# Keg_Cop_-_Devel_SMD.net
KiCad netlist of a schematic drawn in EAGLE
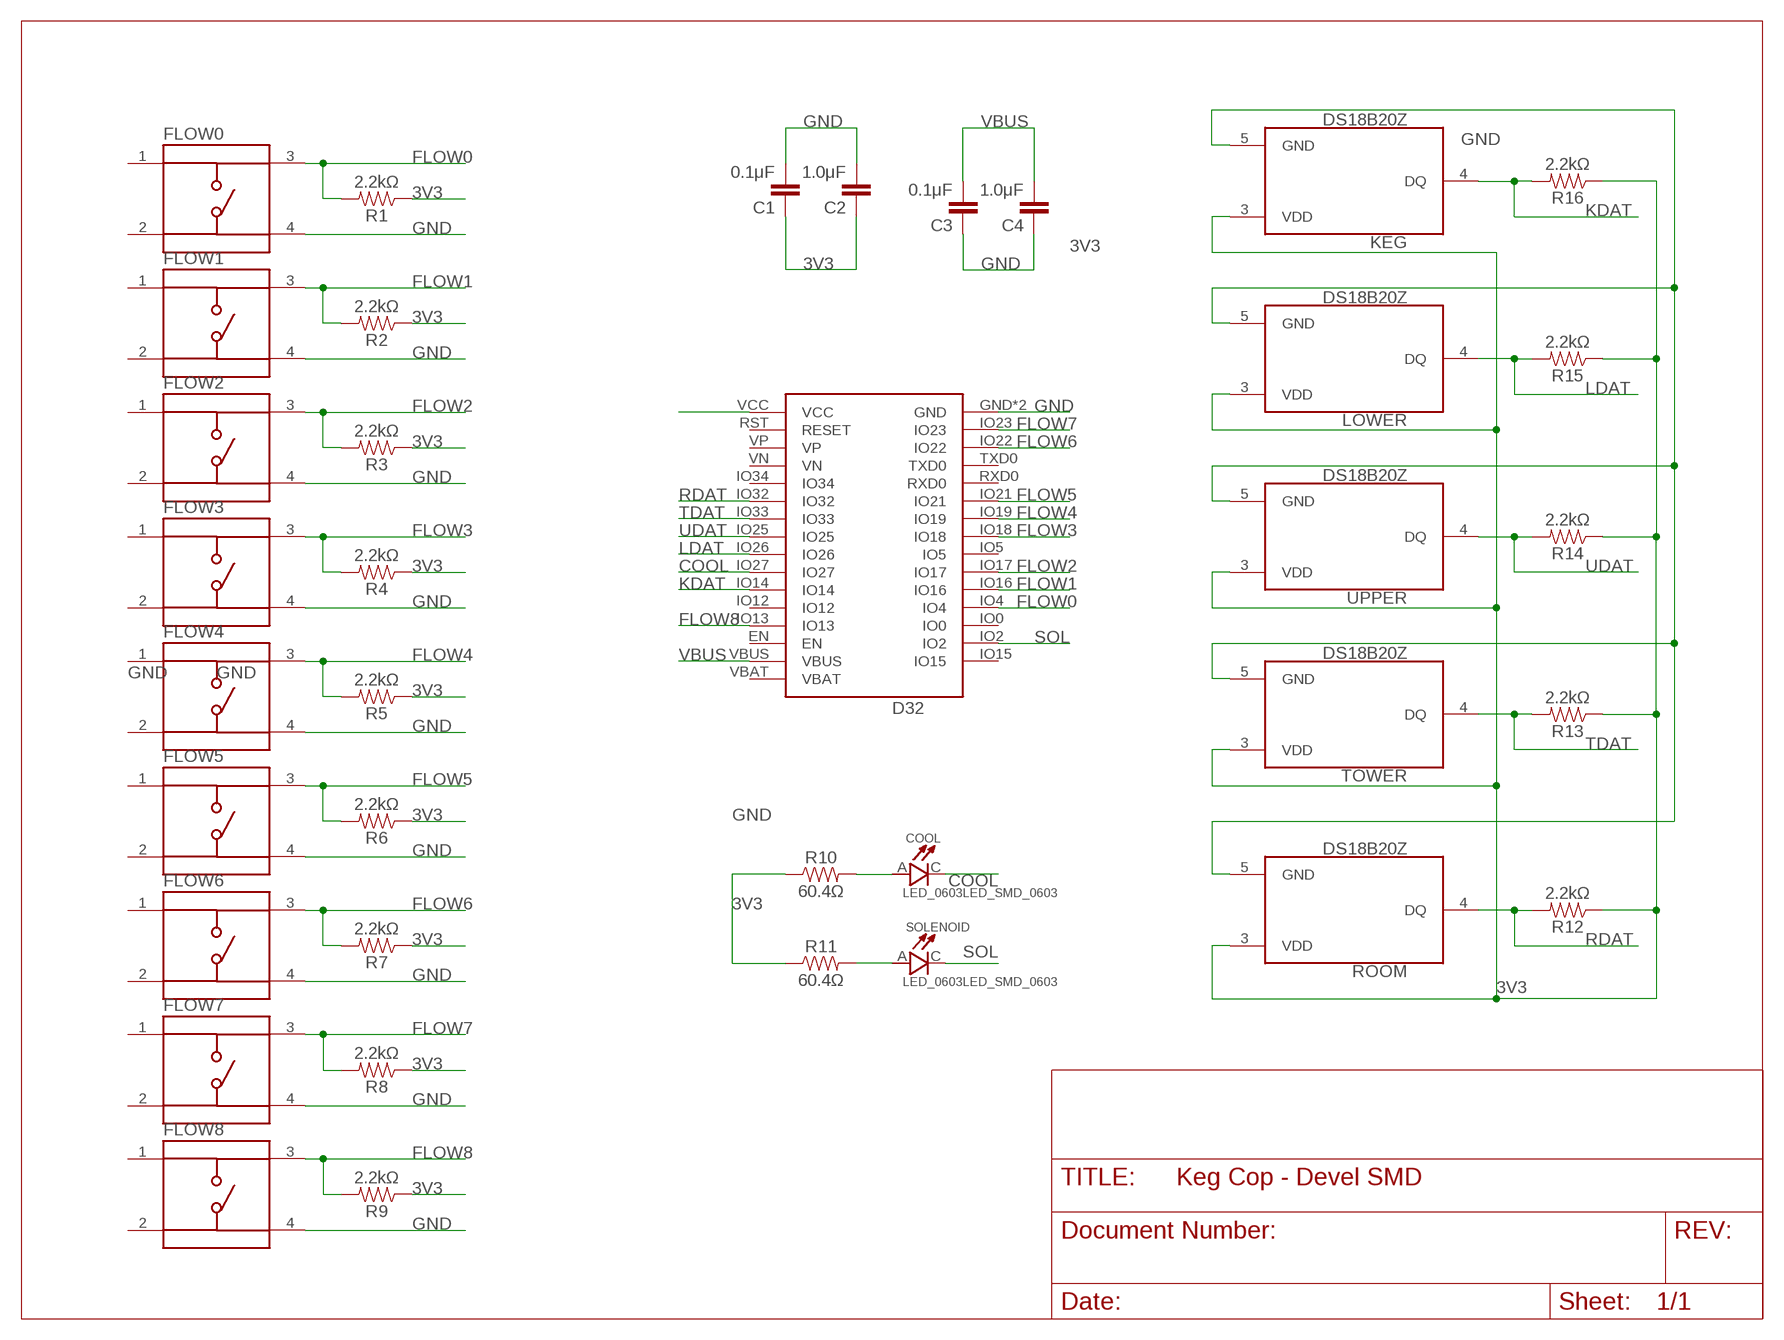
[diagram p0: schematic, sheet 1]

(export (version "E")
  (design (tool "Eeschema 10.0.6"))
  (components
    (comp (ref "C1")
      (value "0.1μF")
      (footprint "eagle-import:SMD-0805")
      (libsource (lib "eagle-import") (part "CAP_SMD0805"))
    )
    (comp (ref "C2")
      (value "1.0μF")
      (footprint "eagle-import:SMD-0805")
      (libsource (lib "eagle-import") (part "CAP_SMD0805"))
    )
    (comp (ref "C3")
      (value "0.1μF")
      (footprint "eagle-import:SMD-0805")
      (libsource (lib "eagle-import") (part "CAP_SMD0805"))
    )
    (comp (ref "C4")
      (value "1.0μF")
      (footprint "eagle-import:SMD-0805")
      (libsource (lib "eagle-import") (part "CAP_SMD0805"))
    )
    (comp (ref "COOL")
      (value "LED_0603LED_SMD_0603")
      (footprint "eagle-import:LED_SMD_0603")
      (fields (field (name "LCSC_PART") "C2286"))
      (libsource (lib "eagle-import") (part "LED_0603LED_SMD_0603"))
    )
    (comp (ref "D32")
      (value "Lolin D32")
      (footprint "eagle-import:D32_NO_BATT")
      (fields (field (name "SPICEPREFIX") "X"))
      (libsource (lib "eagle-import") (part "WEMOS-D32D32_NO_BATT"))
    )
    (comp (ref "FLOW0")
      (value "TS08-66-43-BK-160-SMT-67")
      (footprint "eagle-import:SW_TS08-66-43-BK-160-SMT-67")
      (fields
        (field (name "LCSC_PART") "C2888744")
        (field (name "MF") "BZCN")
        (field (name "MP") "TSD003B04326A03")
      )
      (libsource (lib "eagle-import") (part "TS08-66-43-BK-160-SMT-67"))
    )
    (comp (ref "FLOW1")
      (value "TS08-66-43-BK-160-SMT-67")
      (footprint "eagle-import:SW_TS08-66-43-BK-160-SMT-67")
      (fields
        (field (name "LCSC_PART") "C2888744")
        (field (name "MF") "BZCN")
        (field (name "MP") "TSD003B04326A03")
      )
      (libsource (lib "eagle-import") (part "TS08-66-43-BK-160-SMT-67"))
    )
    (comp (ref "FLOW2")
      (value "TS08-66-43-BK-160-SMT-67")
      (footprint "eagle-import:SW_TS08-66-43-BK-160-SMT-67")
      (fields
        (field (name "LCSC_PART") "C2888744")
        (field (name "MF") "BZCN")
        (field (name "MP") "TSD003B04326A03")
      )
      (libsource (lib "eagle-import") (part "TS08-66-43-BK-160-SMT-67"))
    )
    (comp (ref "FLOW3")
      (value "TS08-66-43-BK-160-SMT-67")
      (footprint "eagle-import:SW_TS08-66-43-BK-160-SMT-67")
      (fields
        (field (name "LCSC_PART") "C2888744")
        (field (name "MF") "BZCN")
        (field (name "MP") "TSD003B04326A03")
      )
      (libsource (lib "eagle-import") (part "TS08-66-43-BK-160-SMT-67"))
    )
    (comp (ref "FLOW4")
      (value "TS08-66-43-BK-160-SMT-67")
      (footprint "eagle-import:SW_TS08-66-43-BK-160-SMT-67")
      (fields
        (field (name "LCSC_PART") "C2888744")
        (field (name "MF") "BZCN")
        (field (name "MP") "TSD003B04326A03")
      )
      (libsource (lib "eagle-import") (part "TS08-66-43-BK-160-SMT-67"))
    )
    (comp (ref "FLOW5")
      (value "TS08-66-43-BK-160-SMT-67")
      (footprint "eagle-import:SW_TS08-66-43-BK-160-SMT-67")
      (fields
        (field (name "LCSC_PART") "C2888744")
        (field (name "MF") "BZCN")
        (field (name "MP") "TSD003B04326A03")
      )
      (libsource (lib "eagle-import") (part "TS08-66-43-BK-160-SMT-67"))
    )
    (comp (ref "FLOW6")
      (value "TS08-66-43-BK-160-SMT-67")
      (footprint "eagle-import:SW_TS08-66-43-BK-160-SMT-67")
      (fields
        (field (name "LCSC_PART") "C2888744")
        (field (name "MF") "BZCN")
        (field (name "MP") "TSD003B04326A03")
      )
      (libsource (lib "eagle-import") (part "TS08-66-43-BK-160-SMT-67"))
    )
    (comp (ref "FLOW7")
      (value "TS08-66-43-BK-160-SMT-67")
      (footprint "eagle-import:SW_TS08-66-43-BK-160-SMT-67")
      (fields
        (field (name "LCSC_PART") "C2888744")
        (field (name "MF") "BZCN")
        (field (name "MP") "TSD003B04326A03")
      )
      (libsource (lib "eagle-import") (part "TS08-66-43-BK-160-SMT-67"))
    )
    (comp (ref "FLOW8")
      (value "TS08-66-43-BK-160-SMT-67")
      (footprint "eagle-import:SW_TS08-66-43-BK-160-SMT-67")
      (fields
        (field (name "LCSC_PART") "C2888744")
        (field (name "MF") "BZCN")
        (field (name "MP") "TSD003B04326A03")
      )
      (libsource (lib "eagle-import") (part "TS08-66-43-BK-160-SMT-67"))
    )
    (comp (ref "KEG")
      (value "DS18B20Z")
      (footprint "eagle-import:SOIC127P600X175-8N")
      (fields (field (name "LCSC_PART") "C695837") (field (name "MF") "Maxim Integrated"))
      (libsource (lib "eagle-import") (part "DS18B20Z"))
    )
    (comp (ref "LOWER")
      (value "DS18B20Z")
      (footprint "eagle-import:SOIC127P600X175-8N")
      (fields (field (name "LCSC_PART") "C695837") (field (name "MF") "Maxim Integrated"))
      (libsource (lib "eagle-import") (part "DS18B20Z"))
    )
    (comp (ref "R1")
      (value "2.2kΩ")
      (footprint "eagle-import:SMD-0805")
      (libsource (lib "eagle-import") (part "RES_SMD0805"))
    )
    (comp (ref "R2")
      (value "2.2kΩ")
      (footprint "eagle-import:SMD-0805")
      (libsource (lib "eagle-import") (part "RES_SMD0805"))
    )
    (comp (ref "R3")
      (value "2.2kΩ")
      (footprint "eagle-import:SMD-0805")
      (libsource (lib "eagle-import") (part "RES_SMD0805"))
    )
    (comp (ref "R4")
      (value "2.2kΩ")
      (footprint "eagle-import:SMD-0805")
      (libsource (lib "eagle-import") (part "RES_SMD0805"))
    )
    (comp (ref "R5")
      (value "2.2kΩ")
      (footprint "eagle-import:SMD-0805")
      (libsource (lib "eagle-import") (part "RES_SMD0805"))
    )
    (comp (ref "R6")
      (value "2.2kΩ")
      (footprint "eagle-import:SMD-0805")
      (libsource (lib "eagle-import") (part "RES_SMD0805"))
    )
    (comp (ref "R7")
      (value "2.2kΩ")
      (footprint "eagle-import:SMD-0805")
      (libsource (lib "eagle-import") (part "RES_SMD0805"))
    )
    (comp (ref "R8")
      (value "2.2kΩ")
      (footprint "eagle-import:SMD-0805")
      (libsource (lib "eagle-import") (part "RES_SMD0805"))
    )
    (comp (ref "R9")
      (value "2.2kΩ")
      (footprint "eagle-import:SMD-0805")
      (libsource (lib "eagle-import") (part "RES_SMD0805"))
    )
    (comp (ref "R10")
      (value "60.4Ω")
      (footprint "eagle-import:SMD-0805")
      (libsource (lib "eagle-import") (part "RES_SMD0805"))
    )
    (comp (ref "R11")
      (value "60.4Ω")
      (footprint "eagle-import:SMD-0805")
      (libsource (lib "eagle-import") (part "RES_SMD0805"))
    )
    (comp (ref "R12")
      (value "2.2kΩ")
      (footprint "eagle-import:SMD-0805")
      (libsource (lib "eagle-import") (part "RES_SMD0805"))
    )
    (comp (ref "R13")
      (value "2.2kΩ")
      (footprint "eagle-import:SMD-0805")
      (libsource (lib "eagle-import") (part "RES_SMD0805"))
    )
    (comp (ref "R14")
      (value "2.2kΩ")
      (footprint "eagle-import:SMD-0805")
      (libsource (lib "eagle-import") (part "RES_SMD0805"))
    )
    (comp (ref "R15")
      (value "2.2kΩ")
      (footprint "eagle-import:SMD-0805")
      (libsource (lib "eagle-import") (part "RES_SMD0805"))
    )
    (comp (ref "R16")
      (value "2.2kΩ")
      (footprint "eagle-import:SMD-0805")
      (libsource (lib "eagle-import") (part "RES_SMD0805"))
    )
    (comp (ref "ROOM")
      (value "DS18B20Z")
      (footprint "eagle-import:SOIC127P600X175-8N")
      (fields (field (name "LCSC_PART") "C695837") (field (name "MF") "Maxim Integrated"))
      (libsource (lib "eagle-import") (part "DS18B20Z"))
    )
    (comp (ref "SOLENOID")
      (value "LED_0603LED_SMD_0603")
      (footprint "eagle-import:LED_SMD_0603")
      (fields (field (name "LCSC_PART") "C2286"))
      (libsource (lib "eagle-import") (part "LED_0603LED_SMD_0603"))
    )
    (comp (ref "TOWER")
      (value "DS18B20Z")
      (footprint "eagle-import:SOIC127P600X175-8N")
      (fields (field (name "LCSC_PART") "C695837") (field (name "MF") "Maxim Integrated"))
      (libsource (lib "eagle-import") (part "DS18B20Z"))
    )
    (comp (ref "UPPER")
      (value "DS18B20Z")
      (footprint "eagle-import:SOIC127P600X175-8N")
      (fields (field (name "LCSC_PART") "C695837") (field (name "MF") "Maxim Integrated"))
      (libsource (lib "eagle-import") (part "DS18B20Z"))
    )
  )
  (nets
    (net (code "1") (name "/3V3") (class "Default")
      (node (ref "C1") (pin "1") (pinfunction "1_1") (pintype "passive"))
      (node (ref "C2") (pin "1") (pinfunction "1_1") (pintype "passive"))
      (node (ref "D32") (pin "VCC") (pinfunction "VCC_VCC") (pintype "power_in"))
      (node (ref "KEG") (pin "3") (pinfunction "VDD_3") (pintype "power_in"))
      (node (ref "LOWER") (pin "3") (pinfunction "VDD_3") (pintype "power_in"))
      (node (ref "R1") (pin "1") (pinfunction "1_1") (pintype "passive"))
      (node (ref "R10") (pin "1") (pinfunction "1_1") (pintype "passive"))
      (node (ref "R11") (pin "1") (pinfunction "1_1") (pintype "passive"))
      (node (ref "R12") (pin "1") (pinfunction "1_1") (pintype "passive"))
      (node (ref "R13") (pin "1") (pinfunction "1_1") (pintype "passive"))
      (node (ref "R14") (pin "1") (pinfunction "1_1") (pintype "passive"))
      (node (ref "R15") (pin "1") (pinfunction "1_1") (pintype "passive"))
      (node (ref "R16") (pin "1") (pinfunction "1_1") (pintype "passive"))
      (node (ref "R2") (pin "1") (pinfunction "1_1") (pintype "passive"))
      (node (ref "R3") (pin "1") (pinfunction "1_1") (pintype "passive"))
      (node (ref "R4") (pin "1") (pinfunction "1_1") (pintype "passive"))
      (node (ref "R5") (pin "1") (pinfunction "1_1") (pintype "passive"))
      (node (ref "R6") (pin "1") (pinfunction "1_1") (pintype "passive"))
      (node (ref "R7") (pin "1") (pinfunction "1_1") (pintype "passive"))
      (node (ref "R8") (pin "1") (pinfunction "1_1") (pintype "passive"))
      (node (ref "R9") (pin "1") (pinfunction "1_1") (pintype "passive"))
      (node (ref "ROOM") (pin "3") (pinfunction "VDD_3") (pintype "power_in"))
      (node (ref "TOWER") (pin "3") (pinfunction "VDD_3") (pintype "power_in"))
      (node (ref "UPPER") (pin "3") (pinfunction "VDD_3") (pintype "power_in"))
    )
    (net (code "2") (name "/COOL") (class "Default")
      (node (ref "COOL") (pin "C") (pinfunction "C_C") (pintype "passive"))
      (node (ref "D32") (pin "IO27") (pinfunction "IO27_IO27") (pintype "bidirectional"))
    )
    (net (code "3") (name "/FLOW0") (class "Default")
      (node (ref "D32") (pin "IO4") (pinfunction "IO4_IO4") (pintype "bidirectional"))
      (node (ref "FLOW0") (pin "3") (pinfunction "3_3") (pintype "passive"))
      (node (ref "R1") (pin "2") (pinfunction "2_2") (pintype "passive"))
    )
    (net (code "4") (name "/FLOW1") (class "Default")
      (node (ref "D32") (pin "IO16") (pinfunction "IO16_IO16") (pintype "bidirectional"))
      (node (ref "FLOW1") (pin "3") (pinfunction "3_3") (pintype "passive"))
      (node (ref "R2") (pin "2") (pinfunction "2_2") (pintype "passive"))
    )
    (net (code "5") (name "/FLOW2") (class "Default")
      (node (ref "D32") (pin "IO17") (pinfunction "IO17_IO17") (pintype "bidirectional"))
      (node (ref "FLOW2") (pin "3") (pinfunction "3_3") (pintype "passive"))
      (node (ref "R3") (pin "2") (pinfunction "2_2") (pintype "passive"))
    )
    (net (code "6") (name "/FLOW3") (class "Default")
      (node (ref "D32") (pin "IO18") (pinfunction "IO18_IO18") (pintype "bidirectional"))
      (node (ref "FLOW3") (pin "3") (pinfunction "3_3") (pintype "passive"))
      (node (ref "R4") (pin "2") (pinfunction "2_2") (pintype "passive"))
    )
    (net (code "7") (name "/FLOW4") (class "Default")
      (node (ref "D32") (pin "IO19") (pinfunction "IO19_IO19") (pintype "bidirectional"))
      (node (ref "FLOW4") (pin "3") (pinfunction "3_3") (pintype "passive"))
      (node (ref "R5") (pin "2") (pinfunction "2_2") (pintype "passive"))
    )
    (net (code "8") (name "/FLOW5") (class "Default")
      (node (ref "D32") (pin "IO21") (pinfunction "IO21_IO21") (pintype "bidirectional"))
      (node (ref "FLOW5") (pin "3") (pinfunction "3_3") (pintype "passive"))
      (node (ref "R6") (pin "2") (pinfunction "2_2") (pintype "passive"))
    )
    (net (code "9") (name "/FLOW6") (class "Default")
      (node (ref "D32") (pin "IO22") (pinfunction "IO22_IO22") (pintype "bidirectional"))
      (node (ref "FLOW6") (pin "3") (pinfunction "3_3") (pintype "passive"))
      (node (ref "R7") (pin "2") (pinfunction "2_2") (pintype "passive"))
    )
    (net (code "10") (name "/FLOW7") (class "Default")
      (node (ref "D32") (pin "IO23") (pinfunction "IO23_IO23") (pintype "bidirectional"))
      (node (ref "FLOW7") (pin "3") (pinfunction "3_3") (pintype "passive"))
      (node (ref "R8") (pin "2") (pinfunction "2_2") (pintype "passive"))
    )
    (net (code "11") (name "/FLOW8") (class "Default")
      (node (ref "D32") (pin "IO13") (pinfunction "IO13_IO13") (pintype "bidirectional"))
      (node (ref "FLOW8") (pin "3") (pinfunction "3_3") (pintype "passive"))
      (node (ref "R9") (pin "2") (pinfunction "2_2") (pintype "passive"))
    )
    (net (code "12") (name "/GND") (class "Default")
      (node (ref "C1") (pin "2") (pinfunction "2_2") (pintype "passive"))
      (node (ref "C2") (pin "2") (pinfunction "2_2") (pintype "passive"))
      (node (ref "C3") (pin "1") (pinfunction "1_1") (pintype "passive"))
      (node (ref "C4") (pin "1") (pinfunction "1_1") (pintype "passive"))
      (node (ref "D32") (pin "GND") (pinfunction "GND_GND") (pintype "power_in"))
      (node (ref "D32") (pin "GND2") (pinfunction "GND_GND2") (pintype "power_in"))
      (node (ref "FLOW0") (pin "4") (pinfunction "4_4") (pintype "passive"))
      (node (ref "FLOW1") (pin "4") (pinfunction "4_4") (pintype "passive"))
      (node (ref "FLOW2") (pin "4") (pinfunction "4_4") (pintype "passive"))
      (node (ref "FLOW3") (pin "4") (pinfunction "4_4") (pintype "passive"))
      (node (ref "FLOW4") (pin "4") (pinfunction "4_4") (pintype "passive"))
      (node (ref "FLOW5") (pin "4") (pinfunction "4_4") (pintype "passive"))
      (node (ref "FLOW6") (pin "4") (pinfunction "4_4") (pintype "passive"))
      (node (ref "FLOW7") (pin "4") (pinfunction "4_4") (pintype "passive"))
      (node (ref "FLOW8") (pin "4") (pinfunction "4_4") (pintype "passive"))
      (node (ref "KEG") (pin "5") (pinfunction "GND_5") (pintype "power_in"))
      (node (ref "LOWER") (pin "5") (pinfunction "GND_5") (pintype "power_in"))
      (node (ref "ROOM") (pin "5") (pinfunction "GND_5") (pintype "power_in"))
      (node (ref "TOWER") (pin "5") (pinfunction "GND_5") (pintype "power_in"))
      (node (ref "UPPER") (pin "5") (pinfunction "GND_5") (pintype "power_in"))
    )
    (net (code "13") (name "/KDAT") (class "Default")
      (node (ref "D32") (pin "IO14") (pinfunction "IO14_IO14") (pintype "bidirectional"))
      (node (ref "KEG") (pin "4") (pinfunction "DQ_4") (pintype "bidirectional"))
      (node (ref "R16") (pin "2") (pinfunction "2_2") (pintype "passive"))
    )
    (net (code "14") (name "/LDAT") (class "Default")
      (node (ref "D32") (pin "IO26") (pinfunction "IO26_IO26") (pintype "bidirectional"))
      (node (ref "LOWER") (pin "4") (pinfunction "DQ_4") (pintype "bidirectional"))
      (node (ref "R15") (pin "2") (pinfunction "2_2") (pintype "passive"))
    )
    (net (code "15") (name "/RDAT") (class "Default")
      (node (ref "D32") (pin "IO32") (pinfunction "IO32_IO32") (pintype "bidirectional"))
      (node (ref "R12") (pin "2") (pinfunction "2_2") (pintype "passive"))
      (node (ref "ROOM") (pin "4") (pinfunction "DQ_4") (pintype "bidirectional"))
    )
    (net (code "16") (name "/SOL") (class "Default")
      (node (ref "D32") (pin "IO2") (pinfunction "IO2_IO2") (pintype "bidirectional"))
      (node (ref "SOLENOID") (pin "C") (pinfunction "C_C") (pintype "passive"))
    )
    (net (code "17") (name "/TDAT") (class "Default")
      (node (ref "D32") (pin "IO33") (pinfunction "IO33_IO33") (pintype "bidirectional"))
      (node (ref "R13") (pin "2") (pinfunction "2_2") (pintype "passive"))
      (node (ref "TOWER") (pin "4") (pinfunction "DQ_4") (pintype "bidirectional"))
    )
    (net (code "18") (name "/UDAT") (class "Default")
      (node (ref "D32") (pin "IO25") (pinfunction "IO25_IO25") (pintype "bidirectional"))
      (node (ref "R14") (pin "2") (pinfunction "2_2") (pintype "passive"))
      (node (ref "UPPER") (pin "4") (pinfunction "DQ_4") (pintype "bidirectional"))
    )
    (net (code "19") (name "/VBUS") (class "Default")
      (node (ref "C3") (pin "2") (pinfunction "2_2") (pintype "passive"))
      (node (ref "C4") (pin "2") (pinfunction "2_2") (pintype "passive"))
      (node (ref "D32") (pin "VBUS") (pinfunction "VBUS_VBUS") (pintype "bidirectional"))
    )
    (net (code "20") (name "Net-(COOL-PadA)") (class "Default")
      (node (ref "COOL") (pin "A") (pinfunction "A_A") (pintype "passive"))
      (node (ref "R10") (pin "2") (pinfunction "2_2") (pintype "passive"))
    )
    (net (code "21") (name "Net-(R11-Pad2)") (class "Default")
      (node (ref "R11") (pin "2") (pinfunction "2_2") (pintype "passive"))
      (node (ref "SOLENOID") (pin "A") (pinfunction "A_A") (pintype "passive"))
    )
    (net (code "22") (name "unconnected-(D32-PadEN)") (class "Default")
      (node (ref "D32") (pin "EN") (pinfunction "EN_EN") (pintype "bidirectional"))
    )
    (net (code "23") (name "unconnected-(D32-PadIO0)") (class "Default")
      (node (ref "D32") (pin "IO0") (pinfunction "IO0_IO0") (pintype "bidirectional"))
    )
    (net (code "24") (name "unconnected-(D32-PadIO5)") (class "Default")
      (node (ref "D32") (pin "IO5") (pinfunction "IO5_IO5") (pintype "bidirectional"))
    )
    (net (code "25") (name "unconnected-(D32-PadIO12)") (class "Default")
      (node (ref "D32") (pin "IO12") (pinfunction "IO12_IO12") (pintype "bidirectional"))
    )
    (net (code "26") (name "unconnected-(D32-PadIO15)") (class "Default")
      (node (ref "D32") (pin "IO15") (pinfunction "IO15_IO15") (pintype "bidirectional"))
    )
    (net (code "27") (name "unconnected-(D32-PadIO34)") (class "Default")
      (node (ref "D32") (pin "IO34") (pinfunction "IO34_IO34") (pintype "bidirectional"))
    )
    (net (code "28") (name "unconnected-(D32-PadRXD0)") (class "Default")
      (node (ref "D32") (pin "RXD0") (pinfunction "RXD0_RXD0") (pintype "input"))
    )
    (net (code "29") (name "unconnected-(D32-PadTXD0)") (class "Default")
      (node (ref "D32") (pin "TXD0") (pinfunction "TXD0_TXD0") (pintype "output"))
    )
    (net (code "30") (name "unconnected-(D32-PadVBAT)") (class "Default")
      (node (ref "D32") (pin "VBAT") (pinfunction "VBAT_VBAT") (pintype "bidirectional"))
    )
    (net (code "31") (name "unconnected-(D32-PadVN)") (class "Default")
      (node (ref "D32") (pin "VN") (pinfunction "VN_VN") (pintype "bidirectional"))
    )
    (net (code "32") (name "unconnected-(D32-PadVP)") (class "Default")
      (node (ref "D32") (pin "VP") (pinfunction "VP_VP") (pintype "bidirectional"))
    )
    (net (code "33") (name "unconnected-(D32-RESET-PadRST)") (class "Default")
      (node (ref "D32") (pin "RST") (pinfunction "RESET_RST") (pintype "bidirectional"))
    )
    (net (code "34") (name "unconnected-(FLOW0-Pad1)") (class "Default")
      (node (ref "FLOW0") (pin "1") (pinfunction "1_1") (pintype "passive"))
    )
    (net (code "35") (name "unconnected-(FLOW0-Pad2)") (class "Default")
      (node (ref "FLOW0") (pin "2") (pinfunction "2_2") (pintype "passive"))
    )
    (net (code "36") (name "unconnected-(FLOW1-Pad1)") (class "Default")
      (node (ref "FLOW1") (pin "1") (pinfunction "1_1") (pintype "passive"))
    )
    (net (code "37") (name "unconnected-(FLOW1-Pad2)") (class "Default")
      (node (ref "FLOW1") (pin "2") (pinfunction "2_2") (pintype "passive"))
    )
    (net (code "38") (name "unconnected-(FLOW2-Pad1)") (class "Default")
      (node (ref "FLOW2") (pin "1") (pinfunction "1_1") (pintype "passive"))
    )
    (net (code "39") (name "unconnected-(FLOW2-Pad2)") (class "Default")
      (node (ref "FLOW2") (pin "2") (pinfunction "2_2") (pintype "passive"))
    )
    (net (code "40") (name "unconnected-(FLOW3-Pad1)") (class "Default")
      (node (ref "FLOW3") (pin "1") (pinfunction "1_1") (pintype "passive"))
    )
    (net (code "41") (name "unconnected-(FLOW3-Pad2)") (class "Default")
      (node (ref "FLOW3") (pin "2") (pinfunction "2_2") (pintype "passive"))
    )
    (net (code "42") (name "unconnected-(FLOW4-Pad1)") (class "Default")
      (node (ref "FLOW4") (pin "1") (pinfunction "1_1") (pintype "passive"))
    )
    (net (code "43") (name "unconnected-(FLOW4-Pad2)") (class "Default")
      (node (ref "FLOW4") (pin "2") (pinfunction "2_2") (pintype "passive"))
    )
    (net (code "44") (name "unconnected-(FLOW5-Pad1)") (class "Default")
      (node (ref "FLOW5") (pin "1") (pinfunction "1_1") (pintype "passive"))
    )
    (net (code "45") (name "unconnected-(FLOW5-Pad2)") (class "Default")
      (node (ref "FLOW5") (pin "2") (pinfunction "2_2") (pintype "passive"))
    )
    (net (code "46") (name "unconnected-(FLOW6-Pad1)") (class "Default")
      (node (ref "FLOW6") (pin "1") (pinfunction "1_1") (pintype "passive"))
    )
    (net (code "47") (name "unconnected-(FLOW6-Pad2)") (class "Default")
      (node (ref "FLOW6") (pin "2") (pinfunction "2_2") (pintype "passive"))
    )
    (net (code "48") (name "unconnected-(FLOW7-Pad1)") (class "Default")
      (node (ref "FLOW7") (pin "1") (pinfunction "1_1") (pintype "passive"))
    )
    (net (code "49") (name "unconnected-(FLOW7-Pad2)") (class "Default")
      (node (ref "FLOW7") (pin "2") (pinfunction "2_2") (pintype "passive"))
    )
    (net (code "50") (name "unconnected-(FLOW8-Pad1)") (class "Default")
      (node (ref "FLOW8") (pin "1") (pinfunction "1_1") (pintype "passive"))
    )
    (net (code "51") (name "unconnected-(FLOW8-Pad2)") (class "Default")
      (node (ref "FLOW8") (pin "2") (pinfunction "2_2") (pintype "passive"))
    )
  )
)
